# motor.net
KiCad netlist of a schematic drawn in EAGLE
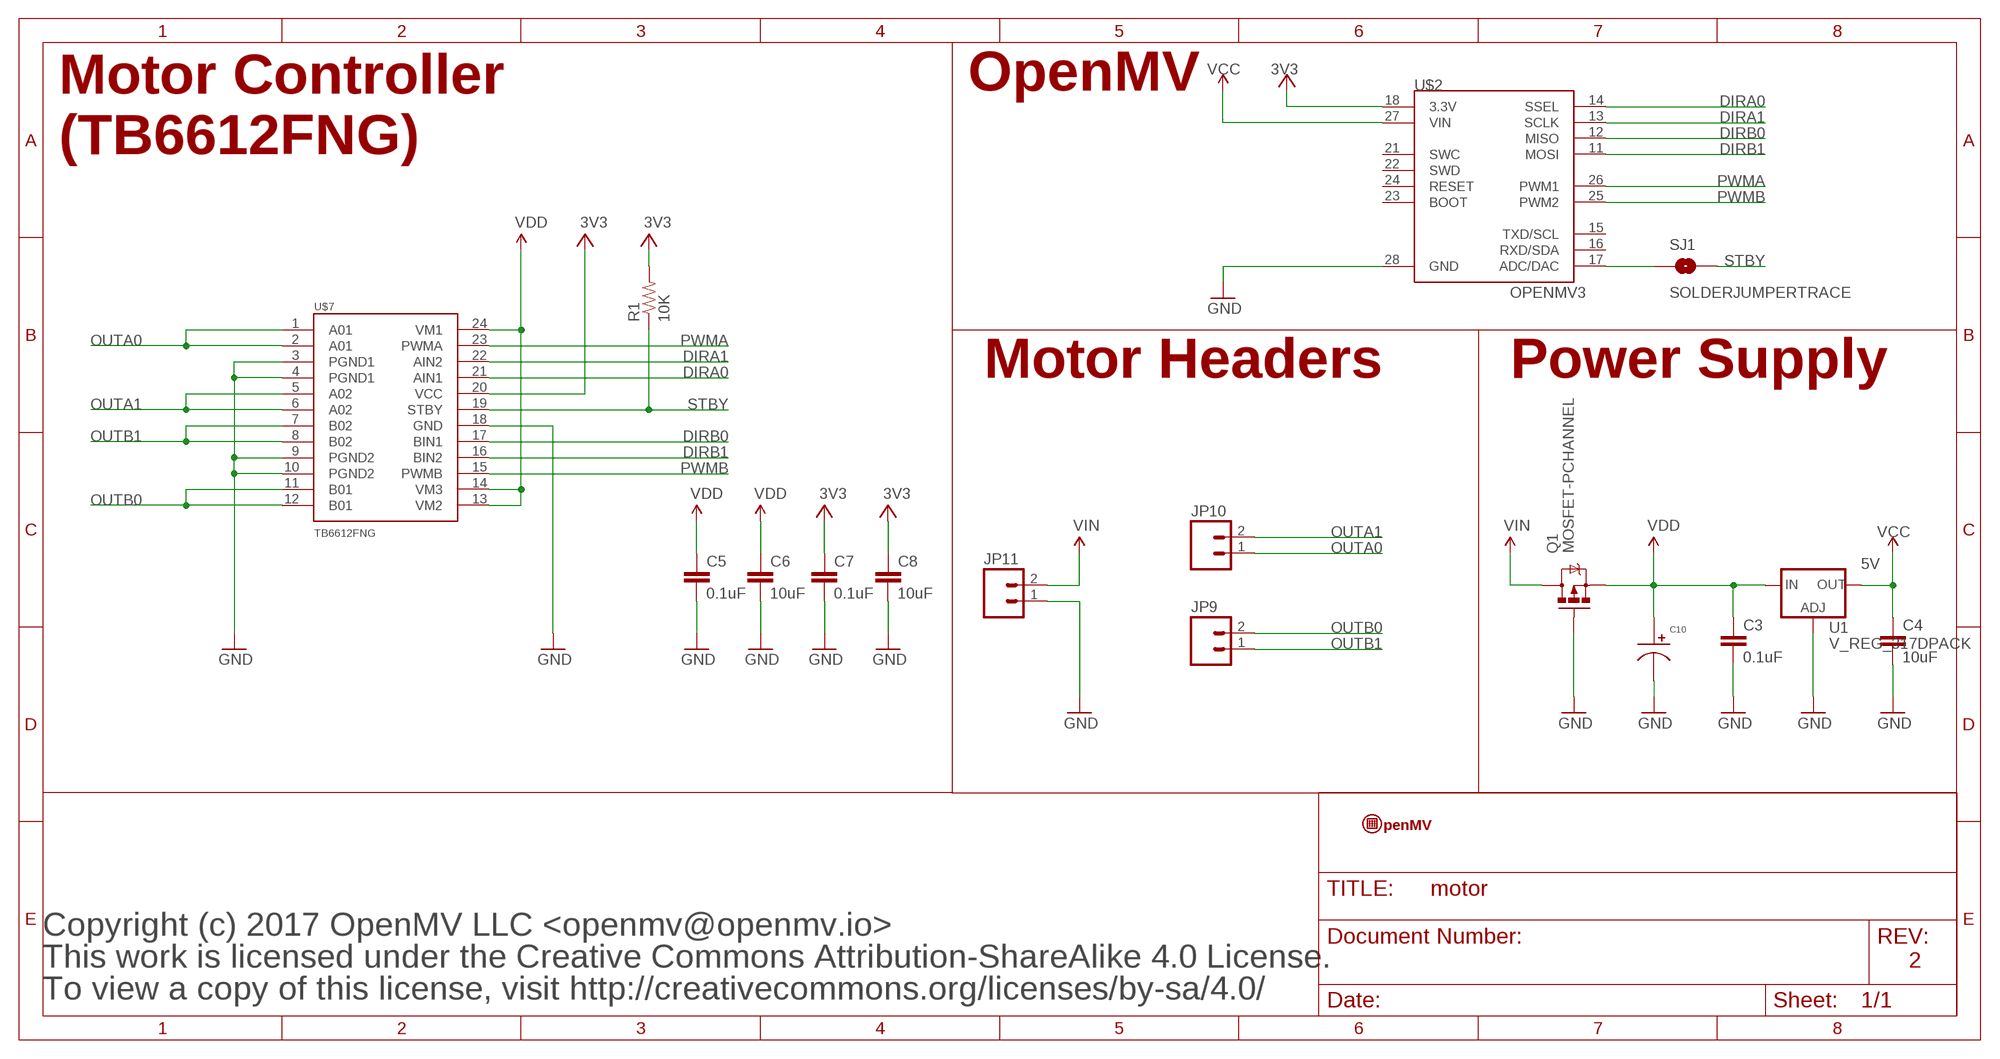
[diagram p0: schematic, sheet 1]

(export (version "E")
  (design (tool "Eeschema 10.0.6"))
  (components
    (comp (ref "C3")
      (value "0.1uF")
      (footprint "eagle-import:0603-CAP")
      (libsource (lib "eagle-import") (part "CAP0603-CAP"))
    )
    (comp (ref "C4")
      (value "10uF")
      (footprint "eagle-import:0805")
      (libsource (lib "eagle-import") (part "CAP0805"))
    )
    (comp (ref "C5")
      (value "0.1uF")
      (footprint "eagle-import:0603-CAP")
      (libsource (lib "eagle-import") (part "CAP0603-CAP"))
    )
    (comp (ref "C6")
      (value "10uF")
      (footprint "eagle-import:0805")
      (libsource (lib "eagle-import") (part "CAP0805"))
    )
    (comp (ref "C7")
      (value "0.1uF")
      (footprint "eagle-import:0603-CAP")
      (libsource (lib "eagle-import") (part "CAP0603-CAP"))
    )
    (comp (ref "C8")
      (value "10uF")
      (footprint "eagle-import:0805")
      (libsource (lib "eagle-import") (part "CAP0805"))
    )
    (comp (ref "C10")
      (value "CAPACITOR_P_10MM")
      (footprint "eagle-import:CP10MM")
      (libsource (lib "eagle-import") (part "CAPACITOR_P_10MM"))
    )
    (comp (ref "JP9")
      (value "M023.5MM")
      (footprint "eagle-import:SCREWTERMINAL-3.5MM-2")
      (libsource (lib "eagle-import") (part "M023.5MM"))
    )
    (comp (ref "JP10")
      (value "M023.5MM")
      (footprint "eagle-import:SCREWTERMINAL-3.5MM-2")
      (libsource (lib "eagle-import") (part "M023.5MM"))
    )
    (comp (ref "JP11")
      (value "M023.5MM")
      (footprint "eagle-import:SCREWTERMINAL-3.5MM-2")
      (libsource (lib "eagle-import") (part "M023.5MM"))
    )
    (comp (ref "Q1")
      (value "MOSFET-PCHANNEL")
      (footprint "eagle-import:SOT23-3")
      (libsource (lib "eagle-import") (part "MOSFET-PCHANNEL"))
    )
    (comp (ref "R1")
      (value "10K")
      (footprint "eagle-import:0603-RES")
      (libsource (lib "eagle-import") (part "10KOHM-1/10W-1%(0603)0603"))
    )
    (comp (ref "SJ1")
      (value "SOLDERJUMPERTRACE")
      (footprint "eagle-import:SJ_2S-TRACE")
      (libsource (lib "eagle-import") (part "SOLDERJUMPERTRACE"))
    )
    (comp (ref "U$2")
      (value "OPENMV3")
      (footprint "eagle-import:OPENMV3")
      (libsource (lib "eagle-import") (part "OPENMV3"))
    )
    (comp (ref "U$7")
      (value "TB6612FNG")
      (footprint "eagle-import:SSOP24")
      (libsource (lib "eagle-import") (part "TB6612FNG"))
    )
    (comp (ref "U$9")
      (value "OPENMV-LOGO")
      (footprint "eagle-import:OPENMV-LOGO")
      (libsource (lib "eagle-import") (part "OPENMV-LOGO"))
    )
    (comp (ref "U1")
      (value "V_REG_317DPACK")
      (footprint "eagle-import:V-REG_DPACK")
      (libsource (lib "eagle-import") (part "V_REG_317DPACK"))
    )
  )
  (nets
    (net (code "1") (name "/DIRA0") (class "Default")
      (node (ref "U$2") (pin "14") (pinfunction "SSEL_14") (pintype "bidirectional"))
      (node (ref "U$7") (pin "21") (pinfunction "AIN1_21") (pintype "bidirectional"))
    )
    (net (code "2") (name "/DIRA1") (class "Default")
      (node (ref "U$2") (pin "13") (pinfunction "SCLK_13") (pintype "bidirectional"))
      (node (ref "U$7") (pin "22") (pinfunction "AIN2_22") (pintype "bidirectional"))
    )
    (net (code "3") (name "/DIRB0") (class "Default")
      (node (ref "U$2") (pin "12") (pinfunction "MISO_12") (pintype "bidirectional"))
      (node (ref "U$7") (pin "17") (pinfunction "BIN1_17") (pintype "bidirectional"))
    )
    (net (code "4") (name "/DIRB1") (class "Default")
      (node (ref "U$2") (pin "11") (pinfunction "MOSI_11") (pintype "bidirectional"))
      (node (ref "U$7") (pin "16") (pinfunction "BIN2_16") (pintype "bidirectional"))
    )
    (net (code "5") (name "/OUTA0") (class "Default")
      (node (ref "JP10") (pin "1") (pinfunction "1_1") (pintype "passive"))
      (node (ref "U$7") (pin "1") (pinfunction "A01_1") (pintype "bidirectional"))
      (node (ref "U$7") (pin "2") (pinfunction "A01_2") (pintype "bidirectional"))
    )
    (net (code "6") (name "/OUTA1") (class "Default")
      (node (ref "JP10") (pin "2") (pinfunction "2_2") (pintype "passive"))
      (node (ref "U$7") (pin "5") (pinfunction "A02_5") (pintype "bidirectional"))
      (node (ref "U$7") (pin "6") (pinfunction "A02_6") (pintype "bidirectional"))
    )
    (net (code "7") (name "/OUTB0") (class "Default")
      (node (ref "JP9") (pin "2") (pinfunction "2_2") (pintype "passive"))
      (node (ref "U$7") (pin "11") (pinfunction "B01_11") (pintype "bidirectional"))
      (node (ref "U$7") (pin "12") (pinfunction "B01_12") (pintype "bidirectional"))
    )
    (net (code "8") (name "/OUTB1") (class "Default")
      (node (ref "JP9") (pin "1") (pinfunction "1_1") (pintype "passive"))
      (node (ref "U$7") (pin "7") (pinfunction "B02_7") (pintype "bidirectional"))
      (node (ref "U$7") (pin "8") (pinfunction "B02_8") (pintype "bidirectional"))
    )
    (net (code "9") (name "/PWMA") (class "Default")
      (node (ref "U$2") (pin "26") (pinfunction "PWM1_26") (pintype "bidirectional"))
      (node (ref "U$7") (pin "23") (pinfunction "PWMA_23") (pintype "bidirectional"))
    )
    (net (code "10") (name "/PWMB") (class "Default")
      (node (ref "U$2") (pin "25") (pinfunction "PWM2_25") (pintype "bidirectional"))
      (node (ref "U$7") (pin "15") (pinfunction "PWMB_15") (pintype "bidirectional"))
    )
    (net (code "11") (name "/STBY") (class "Default")
      (node (ref "R1") (pin "1") (pinfunction "1_1") (pintype "passive"))
      (node (ref "SJ1") (pin "2") (pinfunction "2_2") (pintype "passive"))
      (node (ref "U$7") (pin "19") (pinfunction "STBY_19") (pintype "bidirectional"))
    )
    (net (code "12") (name "3V3") (class "Default")
      (node (ref "C7") (pin "1") (pinfunction "1_1") (pintype "passive"))
      (node (ref "C8") (pin "1") (pinfunction "1_1") (pintype "passive"))
      (node (ref "R1") (pin "2") (pinfunction "2_2") (pintype "passive"))
      (node (ref "U$2") (pin "18") (pinfunction "3.3V_18") (pintype "power_in"))
      (node (ref "U$7") (pin "20") (pinfunction "VCC_20") (pintype "bidirectional"))
    )
    (net (code "13") (name "GND") (class "Default")
      (node (ref "C10") (pin "P$2") (pinfunction "P$2_P$2") (pintype "passive"))
      (node (ref "C3") (pin "2") (pinfunction "2_2") (pintype "passive"))
      (node (ref "C4") (pin "2") (pinfunction "2_2") (pintype "passive"))
      (node (ref "C5") (pin "2") (pinfunction "2_2") (pintype "passive"))
      (node (ref "C6") (pin "2") (pinfunction "2_2") (pintype "passive"))
      (node (ref "C7") (pin "2") (pinfunction "2_2") (pintype "passive"))
      (node (ref "C8") (pin "2") (pinfunction "2_2") (pintype "passive"))
      (node (ref "JP11") (pin "1") (pinfunction "1_1") (pintype "passive"))
      (node (ref "Q1") (pin "1") (pinfunction "G_1") (pintype "passive"))
      (node (ref "U$2") (pin "28") (pinfunction "GND_28") (pintype "power_in"))
      (node (ref "U$7") (pin "10") (pinfunction "PGND2_10") (pintype "bidirectional"))
      (node (ref "U$7") (pin "18") (pinfunction "GND_18") (pintype "bidirectional"))
      (node (ref "U$7") (pin "3") (pinfunction "PGND1_3") (pintype "bidirectional"))
      (node (ref "U$7") (pin "4") (pinfunction "PGND1_4") (pintype "bidirectional"))
      (node (ref "U$7") (pin "9") (pinfunction "PGND2_9") (pintype "bidirectional"))
      (node (ref "U1") (pin "1") (pinfunction "ADJ_1") (pintype "input"))
    )
    (net (code "14") (name "Net-(U$2-ADC{slash}DAC)") (class "Default")
      (node (ref "SJ1") (pin "1") (pinfunction "1_1") (pintype "passive"))
      (node (ref "U$2") (pin "17") (pinfunction "ADC/DAC_17") (pintype "bidirectional"))
    )
    (net (code "15") (name "VCC") (class "Default")
      (node (ref "C4") (pin "1") (pinfunction "1_1") (pintype "passive"))
      (node (ref "U$2") (pin "27") (pinfunction "VIN_27") (pintype "power_in"))
      (node (ref "U1") (pin "4") (pinfunction "OUT_4") (pintype "output"))
    )
    (net (code "16") (name "VDD") (class "Default")
      (node (ref "C10") (pin "P$1") (pinfunction "P$1_P$1") (pintype "passive"))
      (node (ref "C3") (pin "1") (pinfunction "1_1") (pintype "passive"))
      (node (ref "C5") (pin "1") (pinfunction "1_1") (pintype "passive"))
      (node (ref "C6") (pin "1") (pinfunction "1_1") (pintype "passive"))
      (node (ref "Q1") (pin "2") (pinfunction "S_2") (pintype "passive"))
      (node (ref "U$7") (pin "13") (pinfunction "VM2_13") (pintype "bidirectional"))
      (node (ref "U$7") (pin "14") (pinfunction "VM3_14") (pintype "bidirectional"))
      (node (ref "U$7") (pin "24") (pinfunction "VM1_24") (pintype "bidirectional"))
      (node (ref "U1") (pin "3") (pinfunction "IN_3") (pintype "input"))
    )
    (net (code "17") (name "VIN") (class "Default")
      (node (ref "JP11") (pin "2") (pinfunction "2_2") (pintype "passive"))
      (node (ref "Q1") (pin "3") (pinfunction "D_3") (pintype "passive"))
    )
    (net (code "18") (name "unconnected-(U$2-BOOT-Pad23)") (class "Default")
      (node (ref "U$2") (pin "23") (pinfunction "BOOT_23") (pintype "bidirectional"))
    )
    (net (code "19") (name "unconnected-(U$2-RESET-Pad24)") (class "Default")
      (node (ref "U$2") (pin "24") (pinfunction "RESET_24") (pintype "bidirectional"))
    )
    (net (code "20") (name "unconnected-(U$2-RXD{slash}SDA-Pad16)") (class "Default")
      (node (ref "U$2") (pin "16") (pinfunction "RXD/SDA_16") (pintype "bidirectional"))
    )
    (net (code "21") (name "unconnected-(U$2-SWC-Pad21)") (class "Default")
      (node (ref "U$2") (pin "21") (pinfunction "SWC_21") (pintype "bidirectional"))
    )
    (net (code "22") (name "unconnected-(U$2-SWD-Pad22)") (class "Default")
      (node (ref "U$2") (pin "22") (pinfunction "SWD_22") (pintype "bidirectional"))
    )
    (net (code "23") (name "unconnected-(U$2-TXD{slash}SCL-Pad15)") (class "Default")
      (node (ref "U$2") (pin "15") (pinfunction "TXD/SCL_15") (pintype "bidirectional"))
    )
  )
)
